# Power.net
KiCad netlist of a schematic drawn in Altium Designer
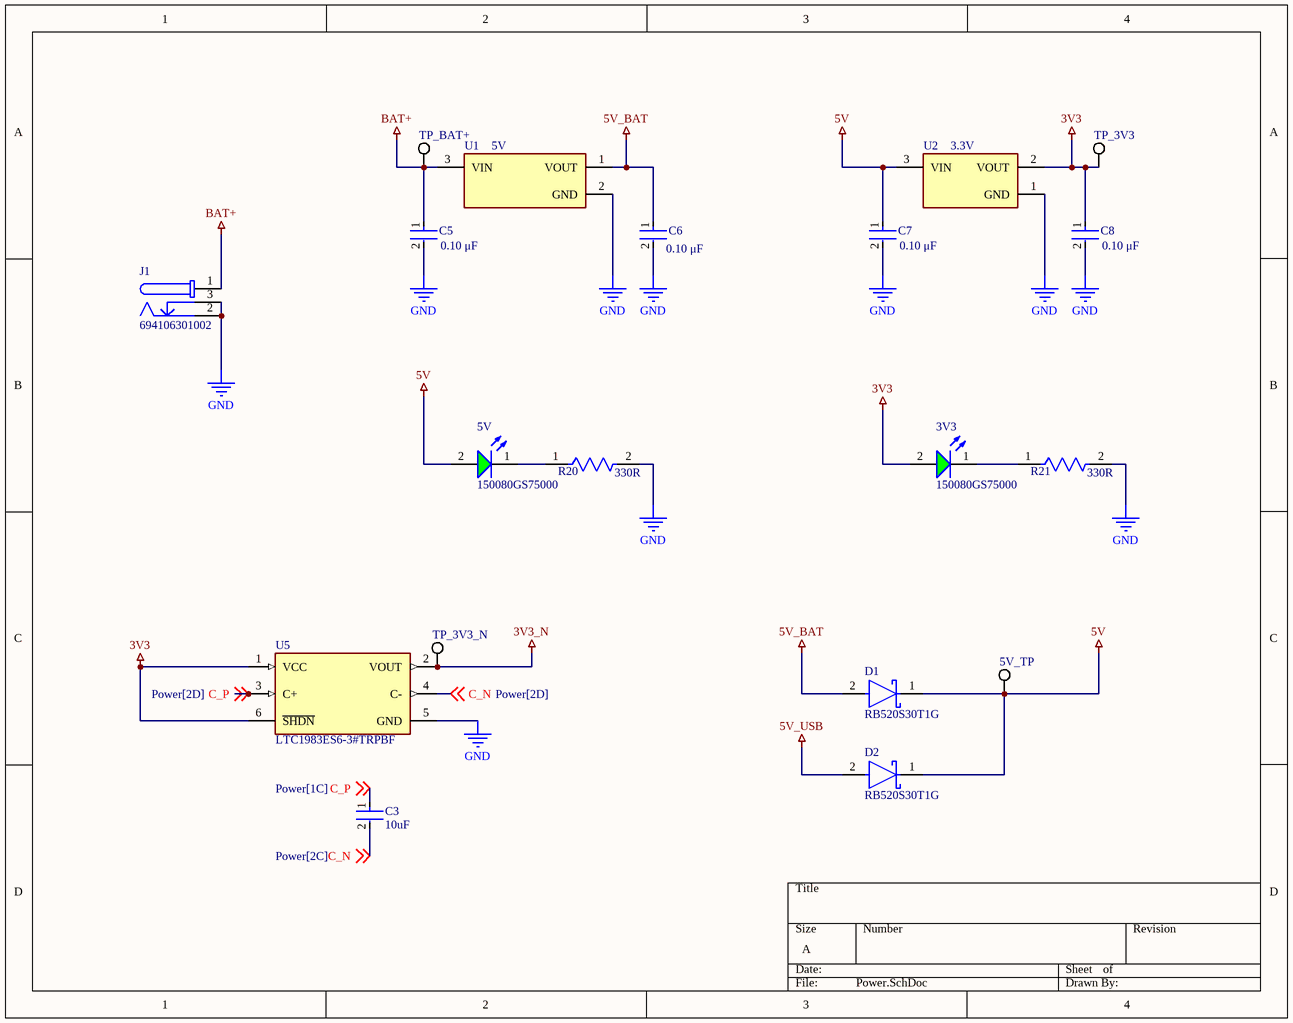
[diagram p0: Power.SchDoc]

(export (version "E")
  (design (tool "Eeschema 10.0.6"))
  (components
    (comp (ref "3V3")
      (value "150080GS75000")
      (footprint "WL-SMCW_0805_150080xx75000")
      (fields (field (name "MANUFACTURER") "Wurth Electronics"))
      (libsource (lib "Altium Content Vault") (part "LED_Green_2A-1K"))
    )
    (comp (ref "5V")
      (value "150080GS75000")
      (footprint "WL-SMCW_0805_150080xx75000")
      (fields (field (name "MANUFACTURER") "Wurth Electronics"))
      (libsource (lib "Altium Content Vault") (part "LED_Green_2A-1K"))
    )
    (comp (ref "5V_TP")
      (value "~")
      (footprint "KSTN-5019_V")
      (description "Test Point, 1 Position SMD, RoHS, Tape and Reel")
      (fields
        (field (name "MANUFACTURER") "Keystone Electronics")
        (field (name "MANUFACTURER PART NUMBER") "5019")
      )
      (libsource (lib "Altium Content Vault") (part "TESTPOINT_WHITE"))
    )
    (comp (ref "C3")
      (value "10uF")
      (footprint "FP-CL05A106MP5NUNC-MFG")
      (description "CAP CER 10UF 10V X5R 0402")
      (fields
        (field (name "OCTOPART") "https://octopart.com/cl05a106mp5nunc-samsung-22457395")
        (field (name "TOLERANCE") "20%")
      )
      (libsource (lib "Altium Content Vault") (part "b4654b650e69147ec39a6b967a45e02"))
    )
    (comp (ref "C5")
      (value "C0603C104K5RACTU")
      (footprint "FP-C0603C-CF-MFG")
      (description "CAP CER 0.1UF 50V X7R 0603")
      (fields
        (field (name "TOLERANCE") "0.1")
        (field (name "MANUFACTURER") "KEMET")
        (field (name "CAPACITANCE") "0.10 μF")
      )
      (libsource (lib "Altium Content Vault") (part "b4654b650e69147ec39a6b967a45e02"))
    )
    (comp (ref "C6")
      (value "C0603C104K5RACTU")
      (footprint "FP-C0603C-CF-MFG")
      (description "CAP CER 0.1UF 50V X7R 0603")
      (fields
        (field (name "TOLERANCE") "0.1")
        (field (name "MANUFACTURER") "KEMET")
        (field (name "CAPACITANCE") "0.10 μF")
      )
      (libsource (lib "Altium Content Vault") (part "b4654b650e69147ec39a6b967a45e02"))
    )
    (comp (ref "C7")
      (value "C0603C104K5RACTU")
      (footprint "FP-C0603C-CF-MFG")
      (description "CAP CER 0.1UF 50V X7R 0603")
      (fields
        (field (name "TOLERANCE") "0.1")
        (field (name "MANUFACTURER") "KEMET")
        (field (name "CAPACITANCE") "0.10 μF")
      )
      (libsource (lib "Altium Content Vault") (part "b4654b650e69147ec39a6b967a45e02"))
    )
    (comp (ref "C8")
      (value "C0603C104K5RACTU")
      (footprint "FP-C0603C-CF-MFG")
      (description "CAP CER 0.1UF 50V X7R 0603")
      (fields
        (field (name "TOLERANCE") "0.1")
        (field (name "MANUFACTURER") "KEMET")
        (field (name "CAPACITANCE") "0.10 μF")
      )
      (libsource (lib "Altium Content Vault") (part "b4654b650e69147ec39a6b967a45e02"))
    )
    (comp (ref "D1")
      (value "RB520S30T1G")
      (footprint "FP-502-01-MFG")
      (description "DIODE SCHOTTKY 30V 200MA SOD523")
      (libsource (lib "Altium Content Vault") (part "1d6ec82d83fb6aee721767c19dac4b9"))
    )
    (comp (ref "D2")
      (value "RB520S30T1G")
      (footprint "FP-502-01-MFG")
      (description "DIODE SCHOTTKY 30V 200MA SOD523")
      (libsource (lib "Altium Content Vault") (part "1d6ec82d83fb6aee721767c19dac4b9"))
    )
    (comp (ref "J1")
      (value "694106301002")
      (footprint "694106301002")
      (fields (field (name "MANUFACTURER") "Wurth Electronics"))
      (libsource (lib "Altium Content Vault") (part "DC Power Jack"))
    )
    (comp (ref "R20")
      (value "CRCW0805330RFKEA")
      (footprint "FP-CRCW0805-e3-MFG")
      (description "RES Thick Film, 330Ω, 1%, 0.125W, 100ppm/°C, 0805")
      (fields
        (field (name "RESISTANCE") "330R")
        (field (name "TOLERANCE") "1%")
        (field (name "MANUFACTURER") "Vishay")
      )
      (libsource (lib "Altium Content Vault") (part "1029c3af85768c4190bb7ad29bc67b5"))
    )
    (comp (ref "R21")
      (value "CRCW0805330RFKEA")
      (footprint "FP-CRCW0805-e3-MFG")
      (description "RES Thick Film, 330Ω, 1%, 0.125W, 100ppm/°C, 0805")
      (fields
        (field (name "RESISTANCE") "330R")
        (field (name "TOLERANCE") "1%")
        (field (name "MANUFACTURER") "Vishay")
      )
      (libsource (lib "Altium Content Vault") (part "1029c3af85768c4190bb7ad29bc67b5"))
    )
    (comp (ref "TP_3V3")
      (value "~")
      (footprint "KSTN-5019_V")
      (description "Test Point, 1 Position SMD, RoHS, Tape and Reel")
      (fields
        (field (name "MANUFACTURER") "Keystone Electronics")
        (field (name "MANUFACTURER PART NUMBER") "5019")
      )
      (libsource (lib "Altium Content Vault") (part "TESTPOINT_WHITE"))
    )
    (comp (ref "TP_3V3_N")
      (value "~")
      (footprint "KSTN-5019_V")
      (description "Test Point, 1 Position SMD, RoHS, Tape and Reel")
      (fields
        (field (name "MANUFACTURER") "Keystone Electronics")
        (field (name "MANUFACTURER PART NUMBER") "5019")
      )
      (libsource (lib "Altium Content Vault") (part "TESTPOINT_WHITE"))
    )
    (comp (ref "TP_BAT+")
      (value "~")
      (footprint "KSTN-5019_V")
      (description "Test Point, 1 Position SMD, RoHS, Tape and Reel")
      (fields
        (field (name "MANUFACTURER") "Keystone Electronics")
        (field (name "MANUFACTURER PART NUMBER") "5019")
      )
      (libsource (lib "Altium Content Vault") (part "TESTPOINT_WHITE"))
    )
    (comp (ref "U1")
      (value "L78L05ACUTR")
      (footprint "FP-SOT-89-7098166-MFG")
      (description "IC REG LINEAR 5V 100MA SOT89-3")
      (fields (field (name "OUTPUT VOLTAGE") "5V") (field (name "MANUFACTURER") "STMicroelectronics"))
      (libsource (lib "Altium Content Vault") (part "ae6bee9076d4e2dbe8e374331bf90c1"))
    )
    (comp (ref "U2")
      (value "AP2120N-3.3TRG1")
      (footprint "FP-SOT23-MFG")
      (description "IC REG LINEAR 3.3V 150MA SOT23")
      (fields
        (field (name "OUTPUT VOLTAGE") "3.3V")
        (field (name "MANUFACTURER") "Diodes Inc.")
        (field (name "OCTOPART") "https://octopart.com/ap2120n-3.3trg1-diodes+inc.-30954573")
      )
      (libsource (lib "Altium Content Vault") (part "340b21d0b7389e2ba8b62ca99e39354"))
    )
    (comp (ref "U5")
      (value "LTC1983ES6-3#TRPBF")
      (footprint "FP-S6-6-05-08-1636-MFG")
      (description "IC REG CHARGE PUMP -3V TSOT23-6")
      (libsource (lib "Altium Content Vault") (part "50886ad60620bc682c538d5ed20c63d"))
    )
  )
  (nets
    (net (code "1") (name "3V3") (class "Default")
      (node (ref "3V3") (pin "2") (pinfunction "A_2") (pintype "passive"))
      (node (ref "C8") (pin "1") (pinfunction "1_1") (pintype "passive"))
      (node (ref "TP_3V3") (pin "1") (pinfunction "1_1") (pintype "passive"))
      (node (ref "U2") (pin "2") (pinfunction "VOUT_2") (pintype "power_in"))
      (node (ref "U5") (pin "1") (pinfunction "VCC_1") (pintype "input"))
      (node (ref "U5") (pin "6") (pinfunction "~{SHDN}_6") (pintype "power_in"))
    )
    (net (code "2") (name "3V3_N") (class "Default")
      (node (ref "TP_3V3_N") (pin "1") (pinfunction "1_1") (pintype "passive"))
      (node (ref "U5") (pin "2") (pinfunction "VOUT_2") (pintype "output"))
    )
    (net (code "3") (name "5V") (class "Default")
      (node (ref "5V") (pin "2") (pinfunction "A_2") (pintype "passive"))
      (node (ref "5V_TP") (pin "1") (pinfunction "1_1") (pintype "passive"))
      (node (ref "C7") (pin "1") (pinfunction "1_1") (pintype "passive"))
      (node (ref "D1") (pin "1") (pinfunction "C_1") (pintype "passive"))
      (node (ref "D2") (pin "1") (pinfunction "C_1") (pintype "passive"))
      (node (ref "U2") (pin "3") (pinfunction "VIN_3") (pintype "power_in"))
    )
    (net (code "4") (name "5V_BAT") (class "Default")
      (node (ref "C6") (pin "1") (pinfunction "1_1") (pintype "passive"))
      (node (ref "D1") (pin "2") (pinfunction "A_2") (pintype "passive"))
      (node (ref "U1") (pin "1") (pinfunction "VOUT_1") (pintype "power_in"))
    )
    (net (code "5") (name "5V_USB") (class "Default")
      (node (ref "D2") (pin "2") (pinfunction "A_2") (pintype "passive"))
    )
    (net (code "6") (name "BAT+") (class "Default")
      (node (ref "C5") (pin "1") (pinfunction "1_1") (pintype "passive"))
      (node (ref "J1") (pin "1") (pinfunction "1_1") (pintype "passive"))
      (node (ref "TP_BAT+") (pin "1") (pinfunction "1_1") (pintype "passive"))
      (node (ref "U1") (pin "3") (pinfunction "VIN_3") (pintype "power_in"))
    )
    (net (code "7") (name "C_N") (class "Default")
      (node (ref "C3") (pin "2") (pinfunction "2_2") (pintype "passive"))
      (node (ref "U5") (pin "4") (pinfunction "C-_4") (pintype "output"))
    )
    (net (code "8") (name "C_P") (class "Default")
      (node (ref "C3") (pin "1") (pinfunction "1_1") (pintype "passive"))
      (node (ref "U5") (pin "3") (pinfunction "C+_3") (pintype "input"))
    )
    (net (code "9") (name "GND") (class "Default")
      (node (ref "C5") (pin "2") (pinfunction "2_2") (pintype "passive"))
      (node (ref "C6") (pin "2") (pinfunction "2_2") (pintype "passive"))
      (node (ref "C7") (pin "2") (pinfunction "2_2") (pintype "passive"))
      (node (ref "C8") (pin "2") (pinfunction "2_2") (pintype "passive"))
      (node (ref "J1") (pin "2") (pinfunction "2_2") (pintype "passive"))
      (node (ref "J1") (pin "3") (pinfunction "3_3") (pintype "passive"))
      (node (ref "R20") (pin "2") (pinfunction "2_2") (pintype "passive"))
      (node (ref "R21") (pin "2") (pinfunction "2_2") (pintype "passive"))
      (node (ref "U1") (pin "2") (pinfunction "GND_2") (pintype "power_in"))
      (node (ref "U2") (pin "1") (pinfunction "GND_1") (pintype "power_in"))
      (node (ref "U5") (pin "5") (pinfunction "GND_5") (pintype "power_in"))
    )
    (net (code "10") (name "Net-(3V3-K)") (class "Default")
      (node (ref "3V3") (pin "1") (pinfunction "K_1") (pintype "passive"))
      (node (ref "R21") (pin "1") (pinfunction "1_1") (pintype "passive"))
    )
    (net (code "11") (name "Net-(5V-K)") (class "Default")
      (node (ref "5V") (pin "1") (pinfunction "K_1") (pintype "passive"))
      (node (ref "R20") (pin "1") (pinfunction "1_1") (pintype "passive"))
    )
  )
)
